# 02_-_Power.net
KiCad netlist of a schematic drawn in Altium Designer
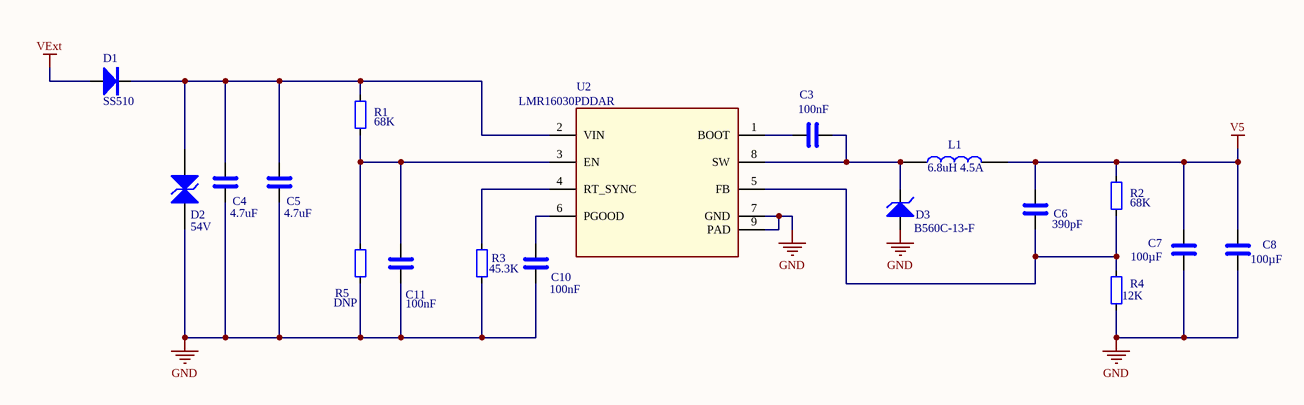
[diagram p0: 02 - Power.SchDoc]

(export (version "E")
  (design (tool "Eeschema 10.0.6"))
  (components
    (comp (ref "C3")
      (value "100nF")
      (footprint "CAP_0603")
      (fields (field (name "LCSC PART") "C6119867"))
      (libsource (lib "WalterFeels") (part "C"))
    )
    (comp (ref "C4")
      (value "4.7uF")
      (footprint "C_1210_3225Metric")
      (fields (field (name "LCSC PART") "C381466"))
      (libsource (lib "WalterFeels") (part "C"))
    )
    (comp (ref "C5")
      (value "4.7uF")
      (footprint "C_1210_3225Metric")
      (fields (field (name "LCSC PART") "C381466"))
      (libsource (lib "WalterFeels") (part "C"))
    )
    (comp (ref "C6")
      (value "390pF")
      (footprint "CAP_0603")
      (description "50V 390pF X7R ±10% 0603 Multilayer Ceramic Capacitors MLCC - SMD/SMT ROHS")
      (fields (field (name "LCSC PART") "C1617"))
      (libsource (lib "WalterFeels") (part "C"))
    )
    (comp (ref "C7")
      (value "100µF")
      (footprint "C_1210_3225Metric")
      (description "6.3V 100uF X5R ±20% 1210 Multilayer Ceramic Capacitors MLCC - SMD/SMT ROHS")
      (fields (field (name "LCSC PART") "C49066"))
      (libsource (lib "Device") (part "C"))
    )
    (comp (ref "C8")
      (value "100µF")
      (footprint "C_1210_3225Metric")
      (description "6.3V 100uF X5R ±20% 1210 Multilayer Ceramic Capacitors MLCC - SMD/SMT ROHS")
      (fields (field (name "LCSC PART") "C49066"))
      (libsource (lib "Device") (part "C"))
    )
    (comp (ref "C10")
      (value "100nF")
      (footprint "CAP_0603")
      (fields (field (name "LCSC PART") "C6119867"))
      (libsource (lib "WalterFeels") (part "C"))
    )
    (comp (ref "C11")
      (value "100nF")
      (footprint "CAP_0603")
      (fields (field (name "LCSC PART") "C6119867"))
      (libsource (lib "WalterFeels") (part "C"))
    )
    (comp (ref "D1")
      (value "SS510")
      (footprint "S1M-13-F")
      (fields (field (name "LCSC PART") "C65010") (field (name "Comment") "DIODE SCHOTTKY 100V 5A DO214AC"))
      (libsource (lib "MIKRODEV_LIBRARY_v2") (part "DIODE SCHOTTKY 100V 5A DO214AC"))
    )
    (comp (ref "D2")
      (value "54V")
      (footprint "SMBJ54CA-HT")
      (description "600W Bidirectional 54V SMB ESD and Surge Protection (TVS/ESD) ROHS")
      (fields (field (name "LCSC PART") "C5353227") (field (name "Comment") "SMBJ54CA-HT"))
      (libsource (lib "MIKRODEV_LIBRARY") (part "DIODE TVS 600W 54V DO214AA SMB"))
    )
    (comp (ref "D3")
      (value "B560C-13-F")
      (footprint "SMC_DIO")
      (description "60V 700mV@5A 5A SMC(DO-214AB) Schottky Diodes ROHS")
      (fields (field (name "LCSC PART") "C85100"))
      (libsource (lib "ahmet") (part "B560C"))
    )
    (comp (ref "L1")
      (value "6.8uH 4.5A")
      (footprint "IHLP2525CZER6R8M01")
      (description "4.5A 6.8uH ±20% 8A SMD,6.5x6.9mm Power Inductors ROHS")
      (fields (field (name "LCSC PART") "C506575"))
      (libsource (lib "MIKRODEV_LIBRARY_v2") (part "FIXED IND 6.8UH 4.5A 60 MOHM SMD"))
    )
    (comp (ref "R1")
      (value "68K")
      (footprint "RES_0603")
      (fields (field (name "LCSC PART") "C114633"))
      (libsource (lib "Device") (part "R"))
    )
    (comp (ref "R2")
      (value "68K")
      (footprint "RES_0603")
      (fields (field (name "LCSC PART") "C114633"))
      (libsource (lib "Device") (part "R"))
    )
    (comp (ref "R3")
      (value "45.3K")
      (footprint "RES_0603")
      (fields (field (name "LCSC PART") "C23058"))
      (libsource (lib "Device") (part "R"))
    )
    (comp (ref "R4")
      (value "12K")
      (footprint "RES_0603")
      (fields (field (name "LCSC PART") "C114659"))
      (libsource (lib "Device") (part "R"))
    )
    (comp (ref "R5") (value "DNP") (footprint "RES_0603") (libsource (lib "Device") (part "R")))
    (comp (ref "U2")
      (value "LMR16030PDDAR")
      (footprint "LMR16030PDDAR")
      (description "Step-down type Adjustable 800mV~50V 3A 4.3V~60V SOIC-8-EP DC-DC Converters ROHS")
      (fields (field (name "LCSC PART") "C90665"))
      (libsource (lib "MIKRODEV_LIBRARY") (part "IC REG BUCK ADJUSTABLE 3A 8SOPWR"))
    )
  )
  (nets
    (net (code "1") (name "GND") (class "Default")
      (node (ref "C10") (pin "2") (pinfunction "2_2") (pintype "passive"))
      (node (ref "C11") (pin "2") (pinfunction "2_2") (pintype "passive"))
      (node (ref "C4") (pin "2") (pinfunction "2_2") (pintype "passive"))
      (node (ref "C5") (pin "2") (pinfunction "2_2") (pintype "passive"))
      (node (ref "C7") (pin "2") (pinfunction "2_2") (pintype "passive"))
      (node (ref "C8") (pin "2") (pinfunction "2_2") (pintype "passive"))
      (node (ref "D2") (pin "1") (pinfunction "A_1") (pintype "passive"))
      (node (ref "D3") (pin "2") (pinfunction "A_2") (pintype "passive"))
      (node (ref "R3") (pin "1") (pinfunction "1_1") (pintype "passive"))
      (node (ref "R4") (pin "1") (pinfunction "1_1") (pintype "passive"))
      (node (ref "R5") (pin "1") (pinfunction "1_1") (pintype "passive"))
      (node (ref "U2") (pin "7") (pinfunction "GND_7") (pintype "passive"))
      (node (ref "U2") (pin "9") (pinfunction "PAD_9") (pintype "passive"))
    )
    (net (code "2") (name "Net-(D1-K)") (class "Default")
      (node (ref "C4") (pin "1") (pinfunction "1_1") (pintype "passive"))
      (node (ref "C5") (pin "1") (pinfunction "1_1") (pintype "passive"))
      (node (ref "D1") (pin "1") (pinfunction "K_1") (pintype "passive"))
      (node (ref "D2") (pin "2") (pinfunction "K_2") (pintype "passive"))
      (node (ref "R1") (pin "2") (pinfunction "2_2") (pintype "passive"))
      (node (ref "U2") (pin "2") (pinfunction "VIN_2") (pintype "passive"))
    )
    (net (code "3") (name "Net-(D3-K)") (class "Default")
      (node (ref "C3") (pin "2") (pinfunction "2_2") (pintype "passive"))
      (node (ref "D3") (pin "1") (pinfunction "K_1") (pintype "passive"))
      (node (ref "L1") (pin "1") (pinfunction "1_1") (pintype "passive"))
      (node (ref "U2") (pin "8") (pinfunction "SW_8") (pintype "passive"))
    )
    (net (code "4") (name "Net-(U2-BOOT)") (class "Default")
      (node (ref "C3") (pin "1") (pinfunction "1_1") (pintype "passive"))
      (node (ref "U2") (pin "1") (pinfunction "BOOT_1") (pintype "passive"))
    )
    (net (code "5") (name "Net-(U2-EN)") (class "Default")
      (node (ref "C11") (pin "1") (pinfunction "1_1") (pintype "passive"))
      (node (ref "R1") (pin "1") (pinfunction "1_1") (pintype "passive"))
      (node (ref "R5") (pin "2") (pinfunction "2_2") (pintype "passive"))
      (node (ref "U2") (pin "3") (pinfunction "EN_3") (pintype "passive"))
    )
    (net (code "6") (name "Net-(U2-FB)") (class "Default")
      (node (ref "C6") (pin "2") (pinfunction "2_2") (pintype "passive"))
      (node (ref "R2") (pin "1") (pinfunction "1_1") (pintype "passive"))
      (node (ref "R4") (pin "2") (pinfunction "2_2") (pintype "passive"))
      (node (ref "U2") (pin "5") (pinfunction "FB_5") (pintype "passive"))
    )
    (net (code "7") (name "Net-(U2-PGOOD)") (class "Default")
      (node (ref "C10") (pin "1") (pinfunction "1_1") (pintype "passive"))
      (node (ref "U2") (pin "6") (pinfunction "PGOOD_6") (pintype "passive"))
    )
    (net (code "8") (name "Net-(U2-RT_SYNC)") (class "Default")
      (node (ref "R3") (pin "2") (pinfunction "2_2") (pintype "passive"))
      (node (ref "U2") (pin "4") (pinfunction "RT_SYNC_4") (pintype "passive"))
    )
    (net (code "9") (name "V5") (class "Default")
      (node (ref "C6") (pin "1") (pinfunction "1_1") (pintype "passive"))
      (node (ref "C7") (pin "1") (pinfunction "1_1") (pintype "passive"))
      (node (ref "C8") (pin "1") (pinfunction "1_1") (pintype "passive"))
      (node (ref "L1") (pin "2") (pinfunction "2_2") (pintype "passive"))
      (node (ref "R2") (pin "2") (pinfunction "2_2") (pintype "passive"))
    )
    (net (code "10") (name "VExt") (class "Default")
      (node (ref "D1") (pin "2") (pinfunction "A_2") (pintype "passive"))
    )
  )
)
